# osborne1.net
KiCad netlist of a schematic drawn in EAGLE
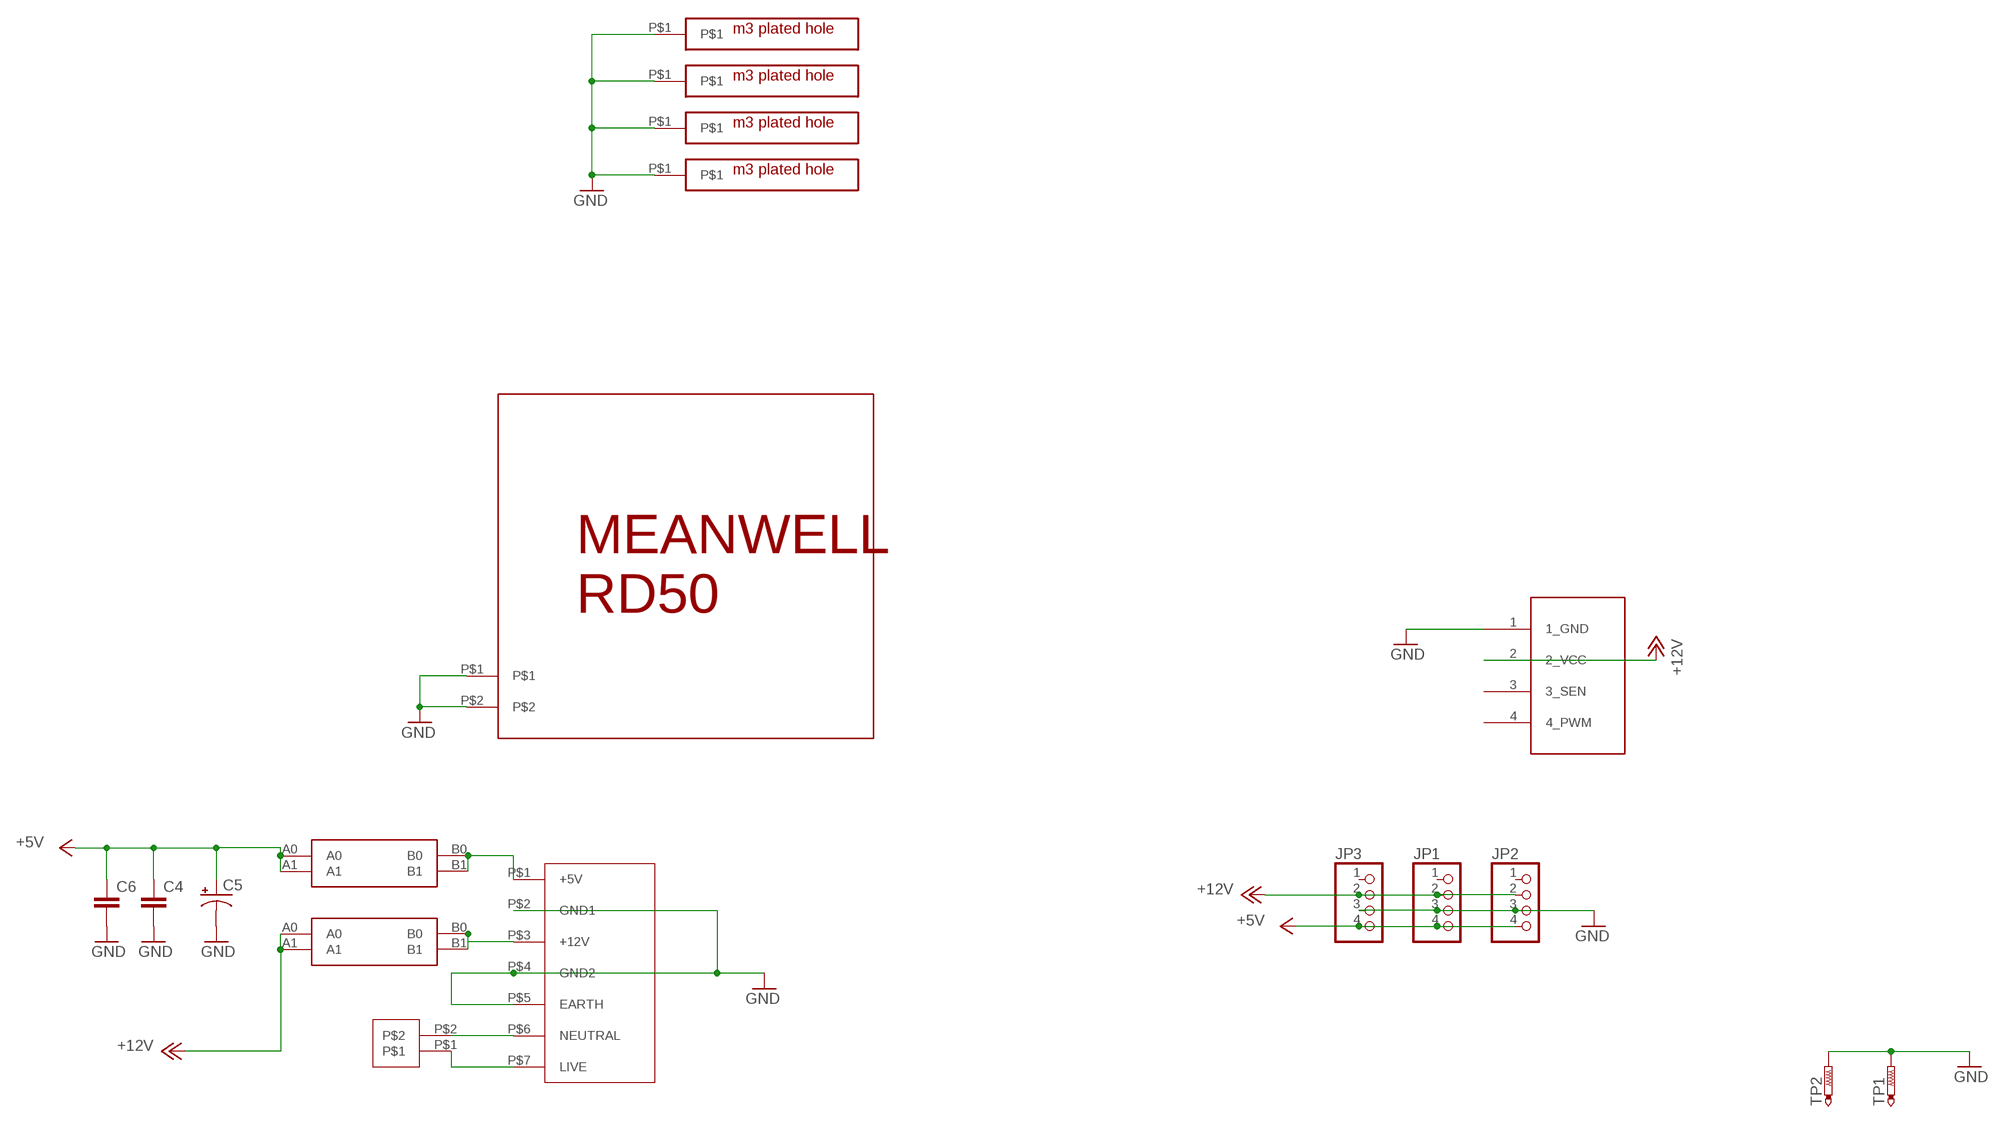
[diagram p0: schematic, sheet 1]

(export (version "E")
  (design (tool "Eeschema 10.0.6"))
  (components
    (comp (ref "C4")
      (value "C5/2.5")
      (footprint "eagle-import:C5B2.5")
      (libsource (lib "eagle-import") (part "C5/2.5"))
    )
    (comp (ref "C5")
      (value "CPOL-USE3.5-8")
      (footprint "eagle-import:E3,5-8")
      (libsource (lib "eagle-import") (part "CPOL-USE3.5-8"))
    )
    (comp (ref "C6")
      (value "C5/2.5")
      (footprint "eagle-import:C5B2.5")
      (libsource (lib "eagle-import") (part "C5/2.5"))
    )
    (comp (ref "JP1")
      (value "PINHD-1X4/90")
      (footprint "eagle-import:1X04_90")
      (libsource (lib "eagle-import") (part "PINHD-1X4/90"))
    )
    (comp (ref "JP2")
      (value "PINHD-1X4/90")
      (footprint "eagle-import:1X04_90")
      (libsource (lib "eagle-import") (part "PINHD-1X4/90"))
    )
    (comp (ref "JP3")
      (value "PINHD-1X4/90")
      (footprint "eagle-import:1X04_90")
      (libsource (lib "eagle-import") (part "PINHD-1X4/90"))
    )
    (comp (ref "JP4")
      (value "4PIN_FAN")
      (footprint "eagle-import:1X04")
      (libsource (lib "eagle-import") (part "4PIN_FAN"))
    )
    (comp (ref "TP1")
      (value "PTR1PAD1-17")
      (footprint "eagle-import:P1-17")
      (libsource (lib "eagle-import") (part "PTR1PAD1-17"))
    )
    (comp (ref "TP2")
      (value "PTR1PAD1-17")
      (footprint "eagle-import:P1-17")
      (libsource (lib "eagle-import") (part "PTR1PAD1-17"))
    )
    (comp (ref "U$1")
      (value "MEANWELL_RD50")
      (footprint "eagle-import:MEANWELL_RD50")
      (libsource (lib "eagle-import") (part "MEANWELL_RD50"))
    )
    (comp (ref "U$2")
      (value "396_2P_LIVE")
      (footprint "eagle-import:396_2P_LIVE")
      (libsource (lib "eagle-import") (part "396_2P_LIVE"))
    )
    (comp (ref "U$3")
      (value "TERM_RD50_MAINS")
      (footprint "eagle-import:TERMINAL9500_MAINS")
      (libsource (lib "eagle-import") (part "TERM_RD50_MAINS"))
    )
    (comp (ref "U$4")
      (value "M3_HOLE_PLATED")
      (footprint "eagle-import:M3_HOLE_PLATED")
      (libsource (lib "eagle-import") (part "M3_HOLE_PLATED"))
    )
    (comp (ref "U$5")
      (value "M3_HOLE_PLATED")
      (footprint "eagle-import:M3_HOLE_PLATED")
      (libsource (lib "eagle-import") (part "M3_HOLE_PLATED"))
    )
    (comp (ref "U$6")
      (value "M3_HOLE_PLATED")
      (footprint "eagle-import:M3_HOLE_PLATED")
      (libsource (lib "eagle-import") (part "M3_HOLE_PLATED"))
    )
    (comp (ref "U$7")
      (value "CAR_FUSE_HOLDER3IN1")
      (footprint "eagle-import:FUSE_HOLDER_3IN1")
      (libsource (lib "eagle-import") (part "CAR_FUSE_HOLDER3IN1"))
    )
    (comp (ref "U$8")
      (value "M3_HOLE_PLATED")
      (footprint "eagle-import:M3_HOLE_PLATED")
      (libsource (lib "eagle-import") (part "M3_HOLE_PLATED"))
    )
    (comp (ref "U$9")
      (value "CAR_FUSE_HOLDER3IN1")
      (footprint "eagle-import:FUSE_HOLDER_3IN1")
      (libsource (lib "eagle-import") (part "CAR_FUSE_HOLDER3IN1"))
    )
  )
  (nets
    (net (code "1") (name "+5V") (class "Default")
      (node (ref "C4") (pin "1") (pinfunction "1_1") (pintype "passive"))
      (node (ref "C5") (pin "+") (pinfunction "+_+") (pintype "passive"))
      (node (ref "C6") (pin "1") (pinfunction "1_1") (pintype "passive"))
      (node (ref "JP1") (pin "4") (pinfunction "4_4") (pintype "passive"))
      (node (ref "JP2") (pin "4") (pinfunction "4_4") (pintype "passive"))
      (node (ref "JP3") (pin "4") (pinfunction "4_4") (pintype "passive"))
      (node (ref "U$9") (pin "A0") (pinfunction "A0_A0") (pintype "bidirectional"))
      (node (ref "U$9") (pin "A1") (pinfunction "A1_A1") (pintype "bidirectional"))
    )
    (net (code "2") (name "+12V") (class "Default")
      (node (ref "JP1") (pin "2") (pinfunction "2_2") (pintype "passive"))
      (node (ref "JP2") (pin "2") (pinfunction "2_2") (pintype "passive"))
      (node (ref "JP3") (pin "2") (pinfunction "2_2") (pintype "passive"))
      (node (ref "JP4") (pin "2") (pinfunction "2_VCC_2") (pintype "passive"))
      (node (ref "U$7") (pin "A0") (pinfunction "A0_A0") (pintype "bidirectional"))
      (node (ref "U$7") (pin "A1") (pinfunction "A1_A1") (pintype "bidirectional"))
    )
    (net (code "3") (name "GND") (class "Default")
      (node (ref "C4") (pin "2") (pinfunction "2_2") (pintype "passive"))
      (node (ref "C5") (pin "-") (pinfunction "-_-") (pintype "passive"))
      (node (ref "C6") (pin "2") (pinfunction "2_2") (pintype "passive"))
      (node (ref "JP1") (pin "3") (pinfunction "3_3") (pintype "passive"))
      (node (ref "JP2") (pin "3") (pinfunction "3_3") (pintype "passive"))
      (node (ref "JP3") (pin "3") (pinfunction "3_3") (pintype "passive"))
      (node (ref "JP4") (pin "1") (pinfunction "1_GND_1") (pintype "passive"))
      (node (ref "TP1") (pin "TP") (pinfunction "TP_TP") (pintype "input"))
      (node (ref "TP2") (pin "TP") (pinfunction "TP_TP") (pintype "input"))
      (node (ref "U$1") (pin "P$1") (pinfunction "P$1_P$1") (pintype "bidirectional"))
      (node (ref "U$1") (pin "P$2") (pinfunction "P$2_P$2") (pintype "bidirectional"))
      (node (ref "U$3") (pin "P$2") (pinfunction "GND1_P$2") (pintype "bidirectional"))
      (node (ref "U$3") (pin "P$4") (pinfunction "GND2_P$4") (pintype "bidirectional"))
      (node (ref "U$3") (pin "P$5") (pinfunction "EARTH_P$5") (pintype "bidirectional"))
      (node (ref "U$4") (pin "P$1") (pinfunction "P$1_P$1") (pintype "bidirectional"))
      (node (ref "U$5") (pin "P$1") (pinfunction "P$1_P$1") (pintype "bidirectional"))
      (node (ref "U$6") (pin "P$1") (pinfunction "P$1_P$1") (pintype "bidirectional"))
      (node (ref "U$8") (pin "P$1") (pinfunction "P$1_P$1") (pintype "bidirectional"))
    )
    (net (code "4") (name "Net-(U$3-+5V)") (class "Default")
      (node (ref "U$3") (pin "P$1") (pinfunction "+5V_P$1") (pintype "bidirectional"))
      (node (ref "U$9") (pin "B0") (pinfunction "B0_B0") (pintype "bidirectional"))
      (node (ref "U$9") (pin "B1") (pinfunction "B1_B1") (pintype "bidirectional"))
    )
    (net (code "5") (name "Net-(U$3-+12V)") (class "Default")
      (node (ref "U$3") (pin "P$3") (pinfunction "+12V_P$3") (pintype "bidirectional"))
      (node (ref "U$7") (pin "B0") (pinfunction "B0_B0") (pintype "bidirectional"))
      (node (ref "U$7") (pin "B1") (pinfunction "B1_B1") (pintype "bidirectional"))
    )
    (net (code "6") (name "Net-(U$3-LIVE)") (class "Default")
      (node (ref "U$2") (pin "P$1") (pinfunction "P$1_P$1") (pintype "bidirectional"))
      (node (ref "U$3") (pin "P$7") (pinfunction "LIVE_P$7") (pintype "bidirectional"))
    )
    (net (code "7") (name "Net-(U$3-NEUTRAL)") (class "Default")
      (node (ref "U$2") (pin "P$2") (pinfunction "P$2_P$2") (pintype "bidirectional"))
      (node (ref "U$3") (pin "P$6") (pinfunction "NEUTRAL_P$6") (pintype "bidirectional"))
    )
    (net (code "8") (name "unconnected-(JP1-Pad1)") (class "Default")
      (node (ref "JP1") (pin "1") (pinfunction "1_1") (pintype "passive"))
    )
    (net (code "9") (name "unconnected-(JP2-Pad1)") (class "Default")
      (node (ref "JP2") (pin "1") (pinfunction "1_1") (pintype "passive"))
    )
    (net (code "10") (name "unconnected-(JP3-Pad1)") (class "Default")
      (node (ref "JP3") (pin "1") (pinfunction "1_1") (pintype "passive"))
    )
    (net (code "11") (name "unconnected-(JP4-3_SEN-Pad3)") (class "Default")
      (node (ref "JP4") (pin "3") (pinfunction "3_SEN_3") (pintype "passive"))
    )
    (net (code "12") (name "unconnected-(JP4-4_PWM-Pad4)") (class "Default")
      (node (ref "JP4") (pin "4") (pinfunction "4_PWM_4") (pintype "passive"))
    )
  )
)
